# DDR3.net
KiCad netlist of a schematic drawn in Altium Designer
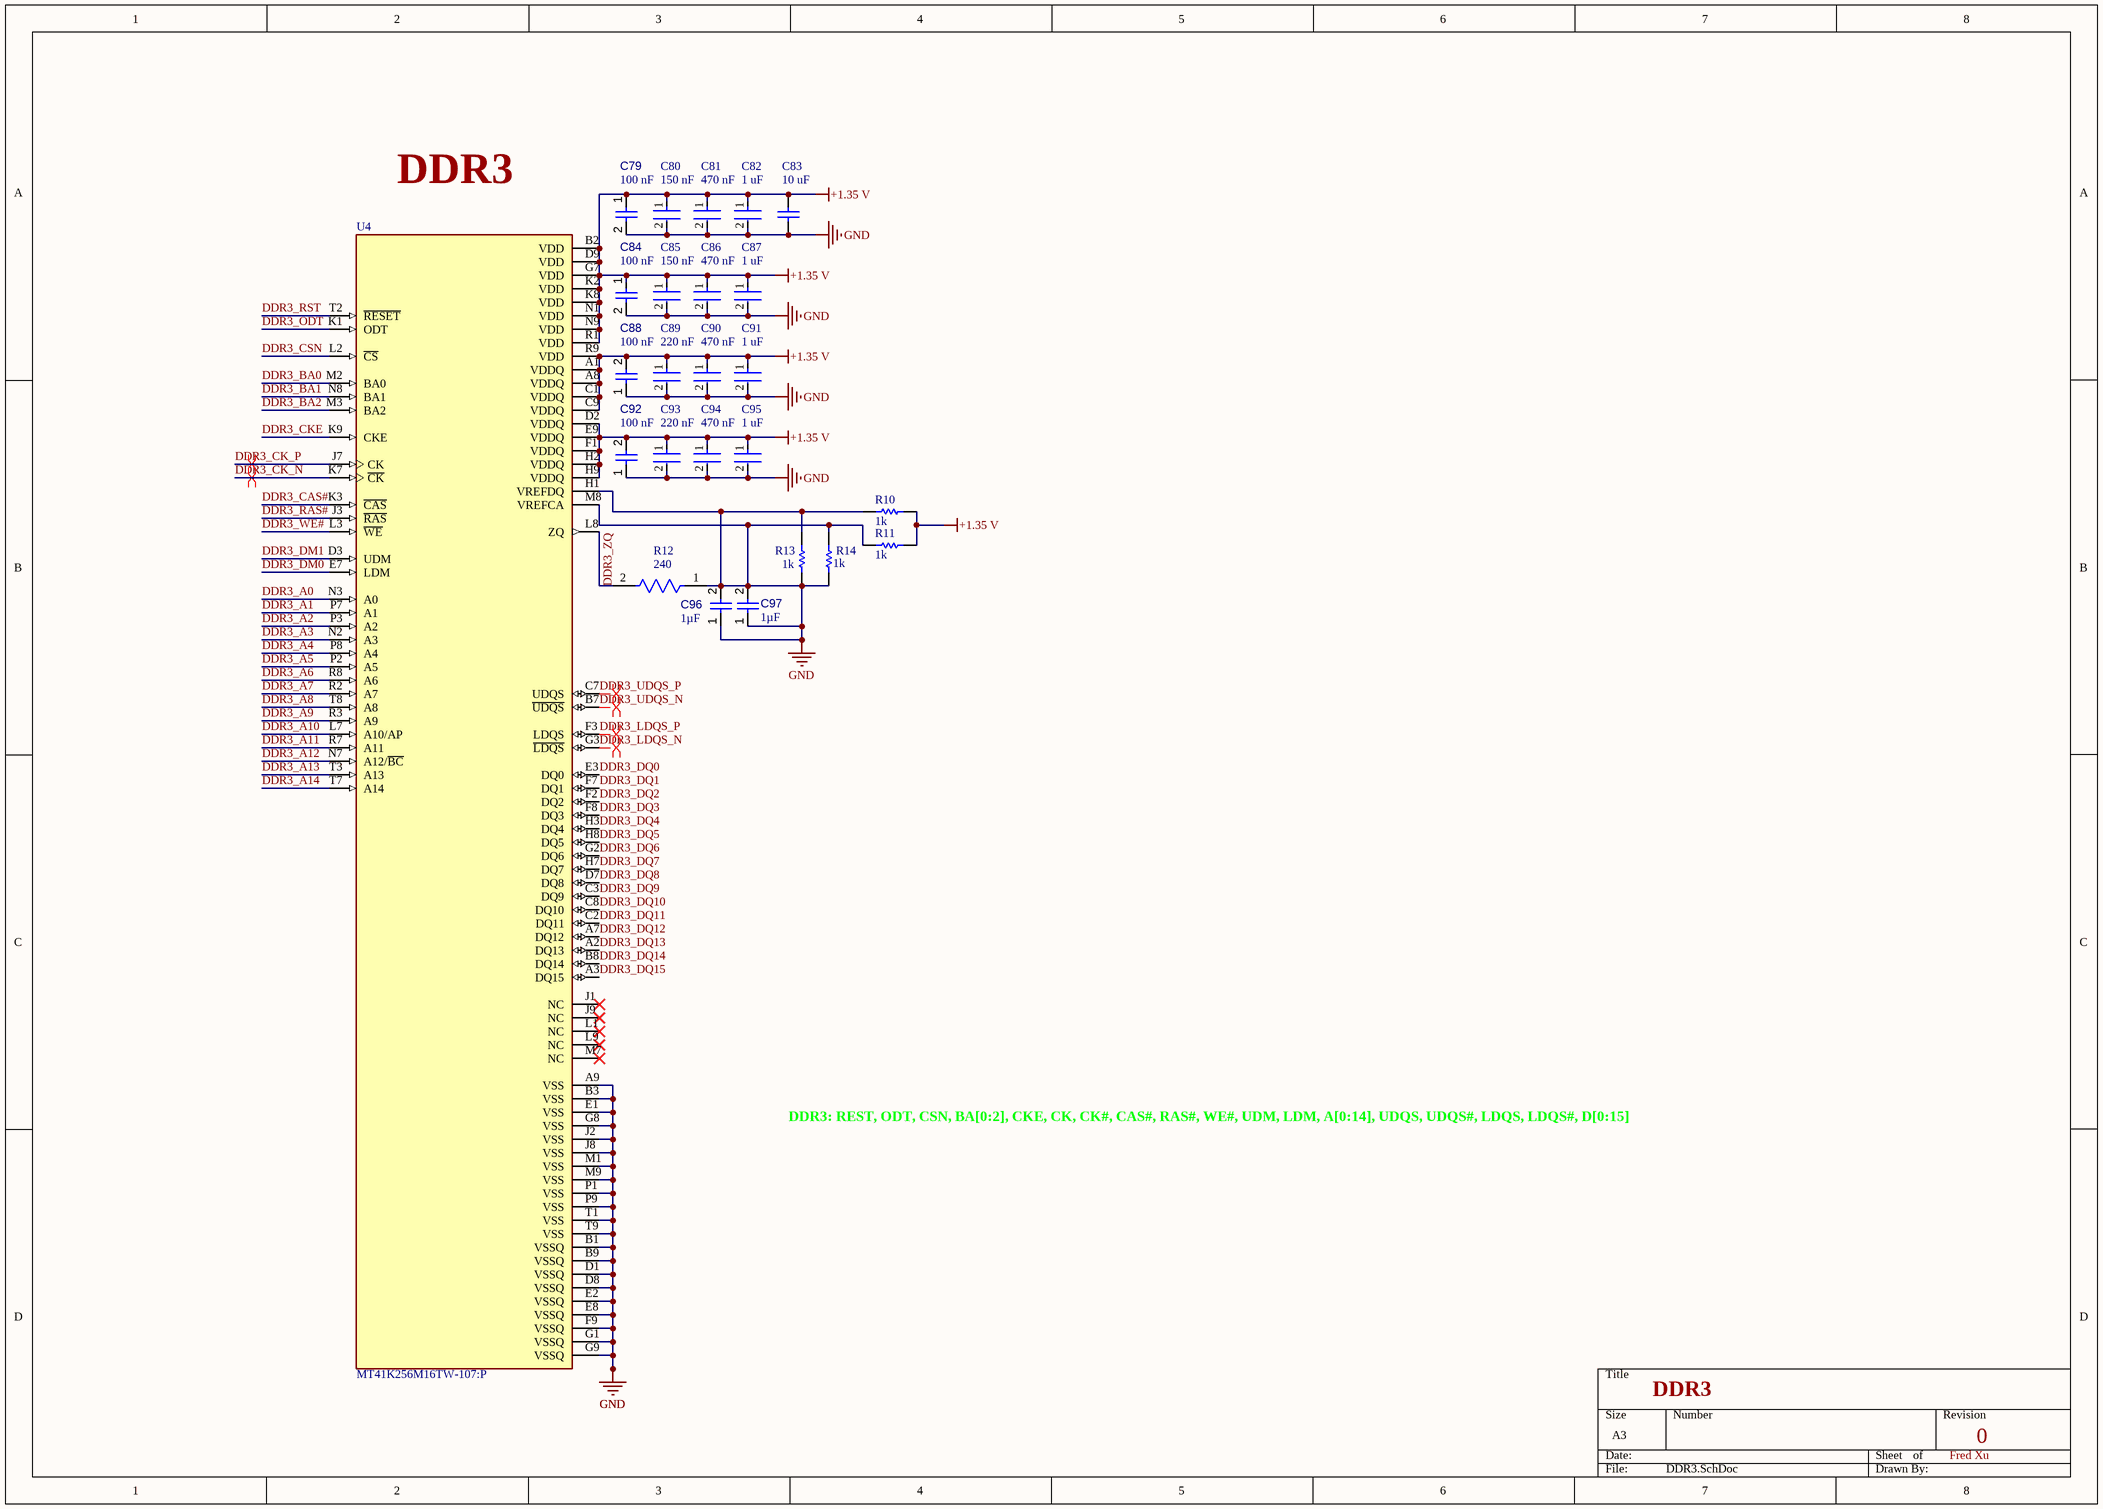
[diagram p0: DDR3.SchDoc]

(export (version "E")
  (design (tool "Eeschema 10.0.6"))
  (components
    (comp (ref "C79")
      (value "100 nF")
      (footprint "CAPC1005X56X25LL10T15")
      (description "Chip Capacitor, 0.1 uF, +/- 5%, 16 V, 0402 (1005 Metric)")
      (fields (field (name "TOLERANCE") "5%") (field (name "Comment") "0.1 uF"))
      (libsource (lib "Fred Xu") (part "CAP-NP-2"))
    )
    (comp (ref "C80")
      (value "150 nF")
      (footprint "FP-GCM155-0_05-MFG")
      (description "Ceramic Capacitor for Automotive 150nF ±20% 16VDC X7R 0402 Paper T/R")
      (libsource (lib "Altium Content Vault") (part "02cd4be3c70576c341d710602a673aa"))
    )
    (comp (ref "C81")
      (value "470 nF")
      (footprint "FP-GRM155-0_05-IPC_B")
      (description "Chip Multilayer Ceramic Capacitors for General Purpose, 0402, 0.47uF, X7R, 15%, 20%, 10V")
      (fields (field (name "TOLERANCE") "20%"))
      (libsource (lib "Altium Content Vault") (part "02cd4be3c70576c341d710602a673aa"))
    )
    (comp (ref "C82")
      (value "1 uF")
      (footprint "FP-GCM155-0_2-MFG")
      (description "Ceramic Capacitor for Automotive 1uF ±20% 10VDC X7S 0402 Paper T/R")
      (libsource (lib "Altium Content Vault") (part "11868f565c42a9108669ba33697ecf6"))
    )
    (comp (ref "C83")
      (value "10 uF")
      (footprint "CAPC2013X152X50NL20T25")
      (fields
        (field (name "PART NUMBER") "0805ZG106ZAT2A")
        (field (name "MANUFACTURER") "AVX Interconnect / Elco")
      )
      (libsource (lib "Altium Content Vault") (part "CAP"))
    )
    (comp (ref "C84")
      (value "100 nF")
      (footprint "CAPC1005X56X25LL10T15")
      (description "Chip Capacitor, 0.1 uF, +/- 5%, 16 V, 0402 (1005 Metric)")
      (fields (field (name "TOLERANCE") "5%") (field (name "Comment") "0.1 uF"))
      (libsource (lib "Fred Xu") (part "CAP-NP-2"))
    )
    (comp (ref "C85")
      (value "150 nF")
      (footprint "FP-GCM155-0_05-MFG")
      (description "Ceramic Capacitor for Automotive 150nF ±20% 16VDC X7R 0402 Paper T/R")
      (libsource (lib "Altium Content Vault") (part "02cd4be3c70576c341d710602a673aa"))
    )
    (comp (ref "C86")
      (value "470 nF")
      (footprint "FP-GRM155-0_05-IPC_B")
      (description "Chip Multilayer Ceramic Capacitors for General Purpose, 0402, 0.47uF, X7R, 15%, 20%, 10V")
      (fields (field (name "TOLERANCE") "20%"))
      (libsource (lib "Altium Content Vault") (part "02cd4be3c70576c341d710602a673aa"))
    )
    (comp (ref "C87")
      (value "1 uF")
      (footprint "FP-GCM155-0_2-MFG")
      (description "Ceramic Capacitor for Automotive 1uF ±20% 10VDC X7S 0402 Paper T/R")
      (libsource (lib "Altium Content Vault") (part "11868f565c42a9108669ba33697ecf6"))
    )
    (comp (ref "C88")
      (value "100 nF")
      (footprint "CAPC1005X56X25LL10T15")
      (description "Chip Capacitor, 0.1 uF, +/- 5%, 16 V, 0402 (1005 Metric)")
      (fields (field (name "TOLERANCE") "5%") (field (name "Comment") "0.1 uF"))
      (libsource (lib "Fred Xu") (part "CAP-NP-2"))
    )
    (comp (ref "C89")
      (value "220 nF")
      (footprint "FP-CGA2B-IPC_B")
      (description "Cap Ceramic 220nF 25V X7R 20% Pad SMD 0402 +125°C Automotive T/R")
      (fields (field (name "TOLERANCE") "20%"))
      (libsource (lib "Altium Content Vault") (part "b4654b650e69147ec39a6b967a45e02"))
    )
    (comp (ref "C90")
      (value "470 nF")
      (footprint "FP-GRM155-0_05-IPC_B")
      (description "Chip Multilayer Ceramic Capacitors for General Purpose, 0402, 0.47uF, X7R, 15%, 20%, 10V")
      (fields (field (name "TOLERANCE") "20%"))
      (libsource (lib "Altium Content Vault") (part "02cd4be3c70576c341d710602a673aa"))
    )
    (comp (ref "C91")
      (value "1 uF")
      (footprint "FP-GCM155-0_2-MFG")
      (description "Ceramic Capacitor for Automotive 1uF ±20% 10VDC X7S 0402 Paper T/R")
      (libsource (lib "Altium Content Vault") (part "11868f565c42a9108669ba33697ecf6"))
    )
    (comp (ref "C92")
      (value "100 nF")
      (footprint "CAPC1005X56X25LL10T15")
      (description "Chip Capacitor, 0.1 uF, +/- 5%, 16 V, 0402 (1005 Metric)")
      (fields (field (name "TOLERANCE") "5%") (field (name "Comment") "0.1 uF"))
      (libsource (lib "Fred Xu") (part "CAP-NP-2"))
    )
    (comp (ref "C93")
      (value "220 nF")
      (footprint "FP-CGA2B-IPC_B")
      (description "Cap Ceramic 220nF 25V X7R 20% Pad SMD 0402 +125°C Automotive T/R")
      (fields (field (name "TOLERANCE") "20%"))
      (libsource (lib "Altium Content Vault") (part "b4654b650e69147ec39a6b967a45e02"))
    )
    (comp (ref "C94")
      (value "470 nF")
      (footprint "FP-GRM155-0_05-IPC_B")
      (description "Chip Multilayer Ceramic Capacitors for General Purpose, 0402, 0.47uF, X7R, 15%, 20%, 10V")
      (fields (field (name "TOLERANCE") "20%"))
      (libsource (lib "Altium Content Vault") (part "02cd4be3c70576c341d710602a673aa"))
    )
    (comp (ref "C95")
      (value "1 uF")
      (footprint "FP-GCM155-0_2-MFG")
      (description "Ceramic Capacitor for Automotive 1uF ±20% 10VDC X7S 0402 Paper T/R")
      (libsource (lib "Altium Content Vault") (part "11868f565c42a9108669ba33697ecf6"))
    )
    (comp (ref "C96")
      (value "1µF")
      (footprint "CAPC0603(1608)100_L")
      (description "Chip Capacitor, 1µF +/-40%, 50V, 0603, Thickness 1 mm")
      (fields (field (name "TOLERANCE") "10%") (field (name "Comment") "Capacitor 1µF +/-40% 50V 0603"))
      (libsource (lib "Fred Xu") (part "CAP-NP-2"))
    )
    (comp (ref "C97")
      (value "1µF")
      (footprint "CAPC0603(1608)100_L")
      (description "Chip Capacitor, 1µF +/-40%, 50V, 0603, Thickness 1 mm")
      (fields (field (name "TOLERANCE") "10%") (field (name "Comment") "Capacitor 1µF +/-40% 50V 0603"))
      (libsource (lib "Fred Xu") (part "CAP-NP-2"))
    )
    (comp (ref "R10")
      (value "1k")
      (footprint "RESC1005X40X25LL05T10")
      (fields (field (name "PART NUMBER") "CRCW04021K00FKEDHP") (field (name "MANUFACTURER") "Vishay Dale"))
      (libsource (lib "Altium Content Vault") (part "RES"))
    )
    (comp (ref "R11")
      (value "1k")
      (footprint "RESC1005X40X25LL05T10")
      (fields (field (name "PART NUMBER") "CRCW04021K00FKEDHP") (field (name "MANUFACTURER") "Vishay Dale"))
      (libsource (lib "Altium Content Vault") (part "RES"))
    )
    (comp (ref "R12")
      (value "240")
      (footprint "FP-RMCF0603-MFG")
      (description "240Ω ±1% 0.1W 0603 Thick Film Chip Resistor AEC-Q200 compliant")
      (fields (field (name "TOLERANCE") "1%"))
      (libsource (lib "Altium Content Vault") (part "1029c3af85768c4190bb7ad29bc67b5"))
    )
    (comp (ref "R13")
      (value "1k")
      (footprint "RESC1005X40X25LL05T10")
      (fields (field (name "PART NUMBER") "CRCW04021K00FKEDHP") (field (name "MANUFACTURER") "Vishay Dale"))
      (libsource (lib "Altium Content Vault") (part "RES"))
    )
    (comp (ref "R14")
      (value "1k")
      (footprint "RESC1005X40X25LL05T10")
      (fields (field (name "PART NUMBER") "CRCW04021K00FKEDHP") (field (name "MANUFACTURER") "Vishay Dale"))
      (libsource (lib "Altium Content Vault") (part "RES"))
    )
    (comp (ref "U4")
      (value "MT41K256M16TW-107:P")
      (footprint "BGA96C80P9X16_1400X800X120")
      (fields (field (name "MF") "{'manufacturer': u'Micron Technology Inc.'}"))
      (libsource (lib "Fred Xu") (part "MT41K256M16TW-107{colon}P"))
    )
  )
  (nets
    (net (code "1") (name "+1.35 V") (class "Default")
      (node (ref "C79") (pin "1") (pinfunction "1_1") (pintype "passive"))
      (node (ref "C80") (pin "1") (pinfunction "1_1") (pintype "passive"))
      (node (ref "C81") (pin "1") (pinfunction "1_1") (pintype "passive"))
      (node (ref "C82") (pin "1") (pinfunction "1_1") (pintype "passive"))
      (node (ref "C83") (pin "2") (pinfunction "2_2") (pintype "passive"))
      (node (ref "C84") (pin "1") (pinfunction "1_1") (pintype "passive"))
      (node (ref "C85") (pin "1") (pinfunction "1_1") (pintype "passive"))
      (node (ref "C86") (pin "1") (pinfunction "1_1") (pintype "passive"))
      (node (ref "C87") (pin "1") (pinfunction "1_1") (pintype "passive"))
      (node (ref "C88") (pin "2") (pinfunction "2_2") (pintype "passive"))
      (node (ref "C89") (pin "1") (pinfunction "1_1") (pintype "passive"))
      (node (ref "C90") (pin "1") (pinfunction "1_1") (pintype "passive"))
      (node (ref "C91") (pin "1") (pinfunction "1_1") (pintype "passive"))
      (node (ref "C92") (pin "2") (pinfunction "2_2") (pintype "passive"))
      (node (ref "C93") (pin "1") (pinfunction "1_1") (pintype "passive"))
      (node (ref "C94") (pin "1") (pinfunction "1_1") (pintype "passive"))
      (node (ref "C95") (pin "1") (pinfunction "1_1") (pintype "passive"))
      (node (ref "R10") (pin "1") (pinfunction "1_1") (pintype "passive"))
      (node (ref "R11") (pin "1") (pinfunction "1_1") (pintype "passive"))
      (node (ref "U4") (pin "A1") (pinfunction "VDDQ_A1") (pintype "power_in"))
      (node (ref "U4") (pin "A8") (pinfunction "VDDQ_A8") (pintype "power_in"))
      (node (ref "U4") (pin "B2") (pinfunction "VDD_B2") (pintype "power_in"))
      (node (ref "U4") (pin "C1") (pinfunction "VDDQ_C1") (pintype "power_in"))
      (node (ref "U4") (pin "C9") (pinfunction "VDDQ_C9") (pintype "power_in"))
      (node (ref "U4") (pin "D2") (pinfunction "VDDQ_D2") (pintype "power_in"))
      (node (ref "U4") (pin "D9") (pinfunction "VDD_D9") (pintype "power_in"))
      (node (ref "U4") (pin "E9") (pinfunction "VDDQ_E9") (pintype "power_in"))
      (node (ref "U4") (pin "F1") (pinfunction "VDDQ_F1") (pintype "power_in"))
      (node (ref "U4") (pin "G7") (pinfunction "VDD_G7") (pintype "power_in"))
      (node (ref "U4") (pin "H2") (pinfunction "VDDQ_H2") (pintype "power_in"))
      (node (ref "U4") (pin "H9") (pinfunction "VDDQ_H9") (pintype "power_in"))
      (node (ref "U4") (pin "K2") (pinfunction "VDD_K2") (pintype "power_in"))
      (node (ref "U4") (pin "K8") (pinfunction "VDD_K8") (pintype "power_in"))
      (node (ref "U4") (pin "N1") (pinfunction "VDD_N1") (pintype "power_in"))
      (node (ref "U4") (pin "N9") (pinfunction "VDD_N9") (pintype "power_in"))
      (node (ref "U4") (pin "R1") (pinfunction "VDD_R1") (pintype "power_in"))
      (node (ref "U4") (pin "R9") (pinfunction "VDD_R9") (pintype "power_in"))
    )
    (net (code "2") (name "/DDR3_A0") (class "Default")
      (node (ref "U4") (pin "N3") (pinfunction "A0_N3") (pintype "input"))
    )
    (net (code "3") (name "/DDR3_A1") (class "Default")
      (node (ref "U4") (pin "P7") (pinfunction "A1_P7") (pintype "input"))
    )
    (net (code "4") (name "/DDR3_A2") (class "Default")
      (node (ref "U4") (pin "P3") (pinfunction "A2_P3") (pintype "input"))
    )
    (net (code "5") (name "/DDR3_A3") (class "Default")
      (node (ref "U4") (pin "N2") (pinfunction "A3_N2") (pintype "input"))
    )
    (net (code "6") (name "/DDR3_A4") (class "Default")
      (node (ref "U4") (pin "P8") (pinfunction "A4_P8") (pintype "input"))
    )
    (net (code "7") (name "/DDR3_A5") (class "Default")
      (node (ref "U4") (pin "P2") (pinfunction "A5_P2") (pintype "input"))
    )
    (net (code "8") (name "/DDR3_A6") (class "Default")
      (node (ref "U4") (pin "R8") (pinfunction "A6_R8") (pintype "input"))
    )
    (net (code "9") (name "/DDR3_A7") (class "Default")
      (node (ref "U4") (pin "R2") (pinfunction "A7_R2") (pintype "input"))
    )
    (net (code "10") (name "/DDR3_A8") (class "Default")
      (node (ref "U4") (pin "T8") (pinfunction "A8_T8") (pintype "input"))
    )
    (net (code "11") (name "/DDR3_A9") (class "Default")
      (node (ref "U4") (pin "R3") (pinfunction "A9_R3") (pintype "input"))
    )
    (net (code "12") (name "/DDR3_A10") (class "Default")
      (node (ref "U4") (pin "L7") (pinfunction "A10/AP_L7") (pintype "input"))
    )
    (net (code "13") (name "/DDR3_A11") (class "Default")
      (node (ref "U4") (pin "R7") (pinfunction "A11_R7") (pintype "input"))
    )
    (net (code "14") (name "/DDR3_A12") (class "Default")
      (node (ref "U4") (pin "N7") (pinfunction "A12/~{BC}_N7") (pintype "input"))
    )
    (net (code "15") (name "/DDR3_A13") (class "Default")
      (node (ref "U4") (pin "T3") (pinfunction "A13_T3") (pintype "input"))
    )
    (net (code "16") (name "/DDR3_A14") (class "Default")
      (node (ref "U4") (pin "T7") (pinfunction "A14_T7") (pintype "input"))
    )
    (net (code "17") (name "/DDR3_BA0") (class "Default")
      (node (ref "U4") (pin "M2") (pinfunction "BA0_M2") (pintype "input"))
    )
    (net (code "18") (name "/DDR3_BA1") (class "Default")
      (node (ref "U4") (pin "N8") (pinfunction "BA1_N8") (pintype "input"))
    )
    (net (code "19") (name "/DDR3_BA2") (class "Default")
      (node (ref "U4") (pin "M3") (pinfunction "BA2_M3") (pintype "input"))
    )
    (net (code "20") (name "/DDR3_CAS#") (class "Default")
      (node (ref "U4") (pin "K3") (pinfunction "~{CAS}_K3") (pintype "input"))
    )
    (net (code "21") (name "/DDR3_CKE") (class "Default")
      (node (ref "U4") (pin "K9") (pinfunction "CKE_K9") (pintype "input"))
    )
    (net (code "22") (name "/DDR3_CK_N") (class "Default")
      (node (ref "U4") (pin "K7") (pinfunction "~{CK}_K7") (pintype "input"))
    )
    (net (code "23") (name "/DDR3_CK_P") (class "Default")
      (node (ref "U4") (pin "J7") (pinfunction "CK_J7") (pintype "input"))
    )
    (net (code "24") (name "/DDR3_CSN") (class "Default")
      (node (ref "U4") (pin "L2") (pinfunction "~{CS}_L2") (pintype "input"))
    )
    (net (code "25") (name "/DDR3_DM0") (class "Default")
      (node (ref "U4") (pin "E7") (pinfunction "LDM_E7") (pintype "input"))
    )
    (net (code "26") (name "/DDR3_DM1") (class "Default")
      (node (ref "U4") (pin "D3") (pinfunction "UDM_D3") (pintype "input"))
    )
    (net (code "27") (name "/DDR3_DQ0") (class "Default")
      (node (ref "U4") (pin "E3") (pinfunction "DQ0_E3") (pintype "bidirectional"))
    )
    (net (code "28") (name "/DDR3_DQ1") (class "Default")
      (node (ref "U4") (pin "F7") (pinfunction "DQ1_F7") (pintype "bidirectional"))
    )
    (net (code "29") (name "/DDR3_DQ2") (class "Default")
      (node (ref "U4") (pin "F2") (pinfunction "DQ2_F2") (pintype "bidirectional"))
    )
    (net (code "30") (name "/DDR3_DQ3") (class "Default")
      (node (ref "U4") (pin "F8") (pinfunction "DQ3_F8") (pintype "bidirectional"))
    )
    (net (code "31") (name "/DDR3_DQ4") (class "Default")
      (node (ref "U4") (pin "H3") (pinfunction "DQ4_H3") (pintype "bidirectional"))
    )
    (net (code "32") (name "/DDR3_DQ5") (class "Default")
      (node (ref "U4") (pin "H8") (pinfunction "DQ5_H8") (pintype "bidirectional"))
    )
    (net (code "33") (name "/DDR3_DQ6") (class "Default")
      (node (ref "U4") (pin "G2") (pinfunction "DQ6_G2") (pintype "bidirectional"))
    )
    (net (code "34") (name "/DDR3_DQ7") (class "Default")
      (node (ref "U4") (pin "H7") (pinfunction "DQ7_H7") (pintype "bidirectional"))
    )
    (net (code "35") (name "/DDR3_DQ8") (class "Default")
      (node (ref "U4") (pin "D7") (pinfunction "DQ8_D7") (pintype "bidirectional"))
    )
    (net (code "36") (name "/DDR3_DQ9") (class "Default")
      (node (ref "U4") (pin "C3") (pinfunction "DQ9_C3") (pintype "bidirectional"))
    )
    (net (code "37") (name "/DDR3_DQ10") (class "Default")
      (node (ref "U4") (pin "C8") (pinfunction "DQ10_C8") (pintype "bidirectional"))
    )
    (net (code "38") (name "/DDR3_DQ11") (class "Default")
      (node (ref "U4") (pin "C2") (pinfunction "DQ11_C2") (pintype "bidirectional"))
    )
    (net (code "39") (name "/DDR3_DQ12") (class "Default")
      (node (ref "U4") (pin "A7") (pinfunction "DQ12_A7") (pintype "bidirectional"))
    )
    (net (code "40") (name "/DDR3_DQ13") (class "Default")
      (node (ref "U4") (pin "A2") (pinfunction "DQ13_A2") (pintype "bidirectional"))
    )
    (net (code "41") (name "/DDR3_DQ14") (class "Default")
      (node (ref "U4") (pin "B8") (pinfunction "DQ14_B8") (pintype "bidirectional"))
    )
    (net (code "42") (name "/DDR3_DQ15") (class "Default")
      (node (ref "U4") (pin "A3") (pinfunction "DQ15_A3") (pintype "bidirectional"))
    )
    (net (code "43") (name "/DDR3_LDQS_N") (class "Default")
      (node (ref "U4") (pin "G3") (pinfunction "~{LDQS}_G3") (pintype "bidirectional"))
    )
    (net (code "44") (name "/DDR3_LDQS_P") (class "Default")
      (node (ref "U4") (pin "F3") (pinfunction "LDQS_F3") (pintype "bidirectional"))
    )
    (net (code "45") (name "/DDR3_ODT") (class "Default")
      (node (ref "U4") (pin "K1") (pinfunction "ODT_K1") (pintype "input"))
    )
    (net (code "46") (name "/DDR3_RAS#") (class "Default")
      (node (ref "U4") (pin "J3") (pinfunction "~{RAS}_J3") (pintype "input"))
    )
    (net (code "47") (name "/DDR3_RST") (class "Default")
      (node (ref "U4") (pin "T2") (pinfunction "~{RESET}_T2") (pintype "input"))
    )
    (net (code "48") (name "/DDR3_UDQS_N") (class "Default")
      (node (ref "U4") (pin "B7") (pinfunction "~{UDQS}_B7") (pintype "bidirectional"))
    )
    (net (code "49") (name "/DDR3_UDQS_P") (class "Default")
      (node (ref "U4") (pin "C7") (pinfunction "UDQS_C7") (pintype "bidirectional"))
    )
    (net (code "50") (name "/DDR3_WE#") (class "Default")
      (node (ref "U4") (pin "L3") (pinfunction "~{WE}_L3") (pintype "input"))
    )
    (net (code "51") (name "/DDR3_ZQ") (class "Default")
      (node (ref "R12") (pin "2") (pinfunction "2_2") (pintype "passive"))
      (node (ref "U4") (pin "L8") (pinfunction "ZQ_L8") (pintype "output"))
    )
    (net (code "52") (name "GND") (class "Default")
      (node (ref "C79") (pin "2") (pinfunction "2_2") (pintype "passive"))
      (node (ref "C80") (pin "2") (pinfunction "2_2") (pintype "passive"))
      (node (ref "C81") (pin "2") (pinfunction "2_2") (pintype "passive"))
      (node (ref "C82") (pin "2") (pinfunction "2_2") (pintype "passive"))
      (node (ref "C83") (pin "1") (pinfunction "1_1") (pintype "passive"))
      (node (ref "C84") (pin "2") (pinfunction "2_2") (pintype "passive"))
      (node (ref "C85") (pin "2") (pinfunction "2_2") (pintype "passive"))
      (node (ref "C86") (pin "2") (pinfunction "2_2") (pintype "passive"))
      (node (ref "C87") (pin "2") (pinfunction "2_2") (pintype "passive"))
      (node (ref "C88") (pin "1") (pinfunction "1_1") (pintype "passive"))
      (node (ref "C89") (pin "2") (pinfunction "2_2") (pintype "passive"))
      (node (ref "C90") (pin "2") (pinfunction "2_2") (pintype "passive"))
      (node (ref "C91") (pin "2") (pinfunction "2_2") (pintype "passive"))
      (node (ref "C92") (pin "1") (pinfunction "1_1") (pintype "passive"))
      (node (ref "C93") (pin "2") (pinfunction "2_2") (pintype "passive"))
      (node (ref "C94") (pin "2") (pinfunction "2_2") (pintype "passive"))
      (node (ref "C95") (pin "2") (pinfunction "2_2") (pintype "passive"))
      (node (ref "C96") (pin "1") (pinfunction "1_1") (pintype "passive"))
      (node (ref "C96") (pin "2") (pinfunction "2_2") (pintype "passive"))
      (node (ref "C97") (pin "1") (pinfunction "1_1") (pintype "passive"))
      (node (ref "C97") (pin "2") (pinfunction "2_2") (pintype "passive"))
      (node (ref "R10") (pin "2") (pinfunction "2_2") (pintype "passive"))
      (node (ref "R11") (pin "2") (pinfunction "2_2") (pintype "passive"))
      (node (ref "R12") (pin "1") (pinfunction "1_1") (pintype "passive"))
      (node (ref "R13") (pin "1") (pinfunction "1_1") (pintype "passive"))
      (node (ref "R13") (pin "2") (pinfunction "2_2") (pintype "passive"))
      (node (ref "R14") (pin "1") (pinfunction "1_1") (pintype "passive"))
      (node (ref "R14") (pin "2") (pinfunction "2_2") (pintype "passive"))
      (node (ref "U4") (pin "A9") (pinfunction "VSS_A9") (pintype "power_in"))
      (node (ref "U4") (pin "B1") (pinfunction "VSSQ_B1") (pintype "power_in"))
      (node (ref "U4") (pin "B3") (pinfunction "VSS_B3") (pintype "power_in"))
      (node (ref "U4") (pin "B9") (pinfunction "VSSQ_B9") (pintype "power_in"))
      (node (ref "U4") (pin "D1") (pinfunction "VSSQ_D1") (pintype "power_in"))
      (node (ref "U4") (pin "D8") (pinfunction "VSSQ_D8") (pintype "power_in"))
      (node (ref "U4") (pin "E1") (pinfunction "VSS_E1") (pintype "power_in"))
      (node (ref "U4") (pin "E2") (pinfunction "VSSQ_E2") (pintype "power_in"))
      (node (ref "U4") (pin "E8") (pinfunction "VSSQ_E8") (pintype "power_in"))
      (node (ref "U4") (pin "F9") (pinfunction "VSSQ_F9") (pintype "power_in"))
      (node (ref "U4") (pin "G1") (pinfunction "VSSQ_G1") (pintype "power_in"))
      (node (ref "U4") (pin "G8") (pinfunction "VSS_G8") (pintype "power_in"))
      (node (ref "U4") (pin "G9") (pinfunction "VSSQ_G9") (pintype "power_in"))
      (node (ref "U4") (pin "H1") (pinfunction "VREFDQ_H1") (pintype "power_in"))
      (node (ref "U4") (pin "J2") (pinfunction "VSS_J2") (pintype "power_in"))
      (node (ref "U4") (pin "J8") (pinfunction "VSS_J8") (pintype "power_in"))
      (node (ref "U4") (pin "M1") (pinfunction "VSS_M1") (pintype "power_in"))
      (node (ref "U4") (pin "M8") (pinfunction "VREFCA_M8") (pintype "power_in"))
      (node (ref "U4") (pin "M9") (pinfunction "VSS_M9") (pintype "power_in"))
      (node (ref "U4") (pin "P1") (pinfunction "VSS_P1") (pintype "power_in"))
      (node (ref "U4") (pin "P9") (pinfunction "VSS_P9") (pintype "power_in"))
      (node (ref "U4") (pin "T1") (pinfunction "VSS_T1") (pintype "power_in"))
      (node (ref "U4") (pin "T9") (pinfunction "VSS_T9") (pintype "power_in"))
    )
    (net (code "53") (name "unconnected-(U4-NC-PadJ1)") (class "Default")
      (node (ref "U4") (pin "J1") (pinfunction "NC_J1") (pintype "passive+no_connect"))
    )
    (net (code "54") (name "unconnected-(U4-NC-PadJ9)") (class "Default")
      (node (ref "U4") (pin "J9") (pinfunction "NC_J9") (pintype "passive+no_connect"))
    )
    (net (code "55") (name "unconnected-(U4-NC-PadL1)") (class "Default")
      (node (ref "U4") (pin "L1") (pinfunction "NC_L1") (pintype "passive+no_connect"))
    )
    (net (code "56") (name "unconnected-(U4-NC-PadL9)") (class "Default")
      (node (ref "U4") (pin "L9") (pinfunction "NC_L9") (pintype "passive+no_connect"))
    )
    (net (code "57") (name "unconnected-(U4-NC-PadM7)") (class "Default")
      (node (ref "U4") (pin "M7") (pinfunction "NC_M7") (pintype "passive+no_connect"))
    )
  )
)
